# Schematic1P1.net
KiCad netlist of a schematic drawn in Altium Designer
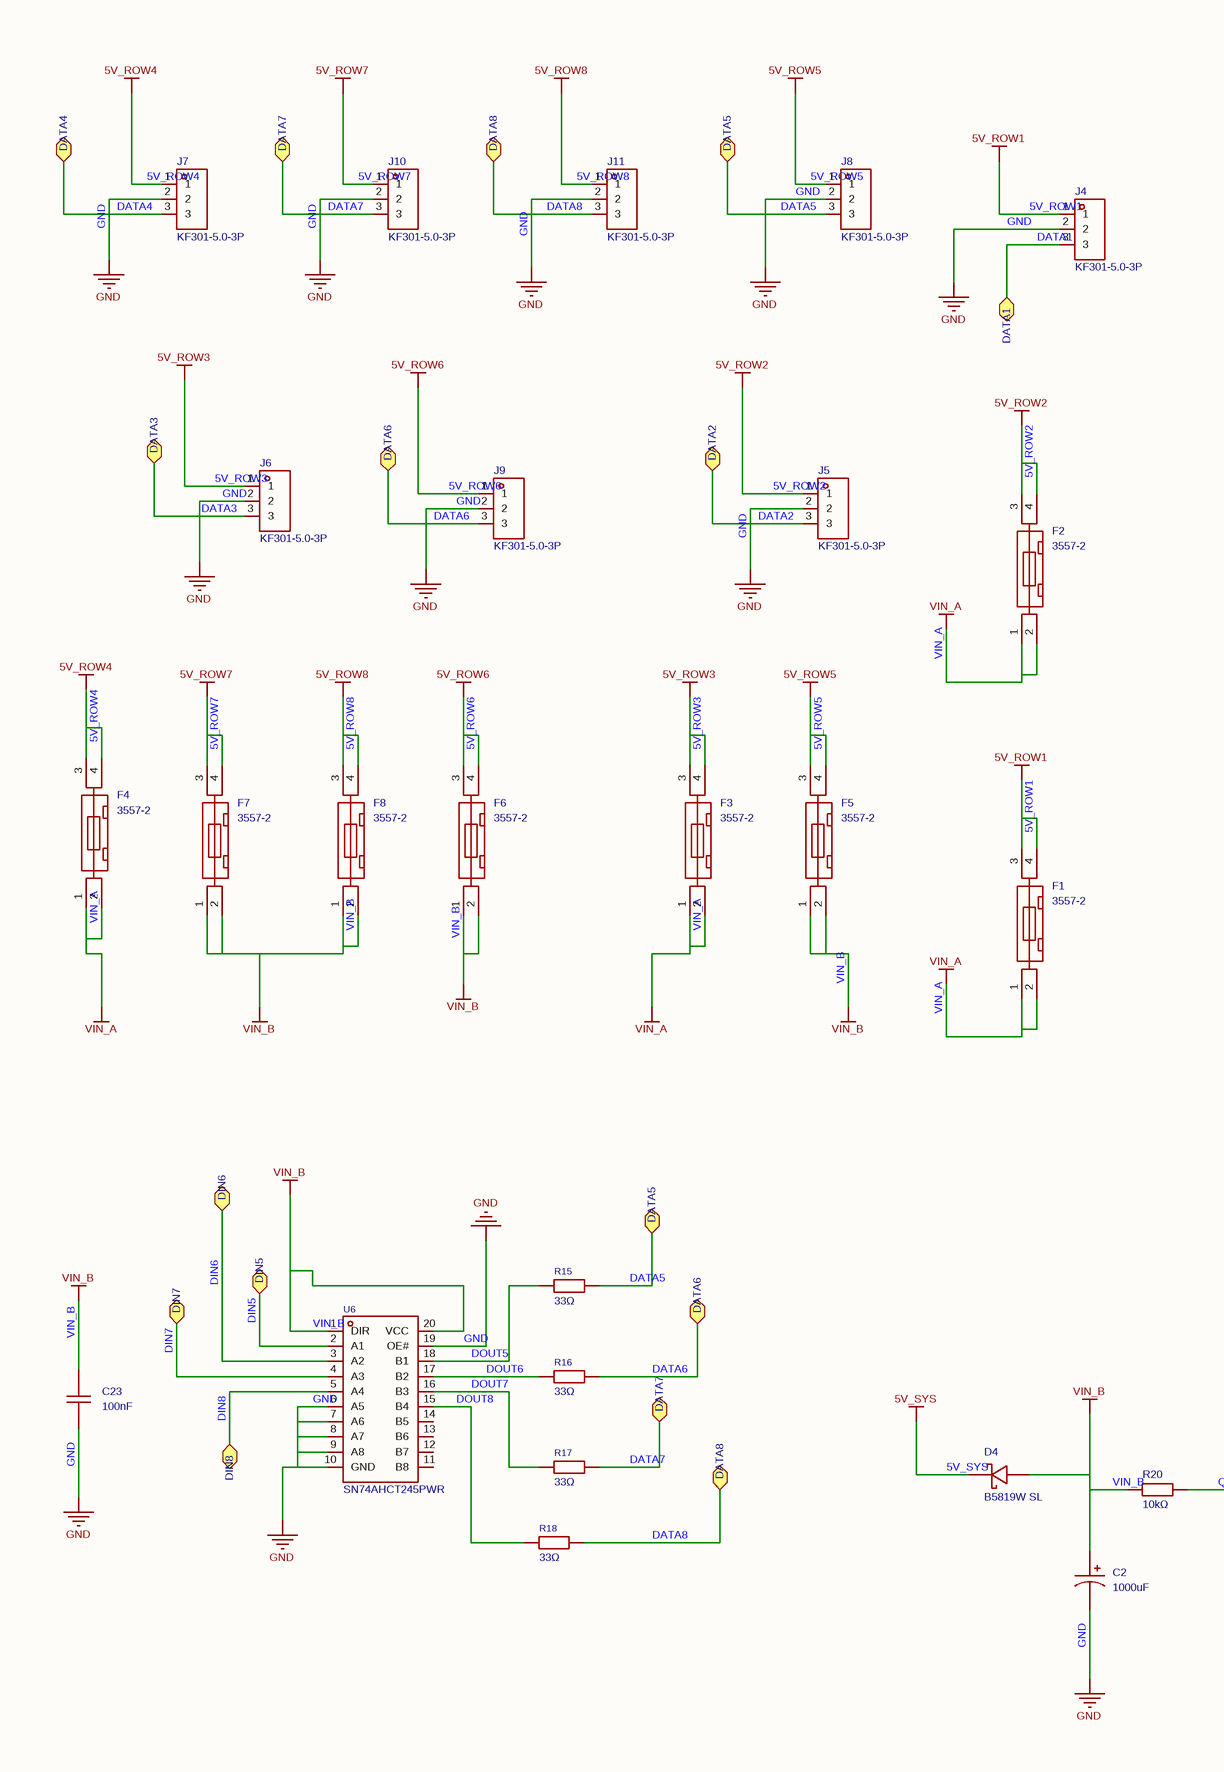
[diagram p0: Schematic1P1.schdoc, left]
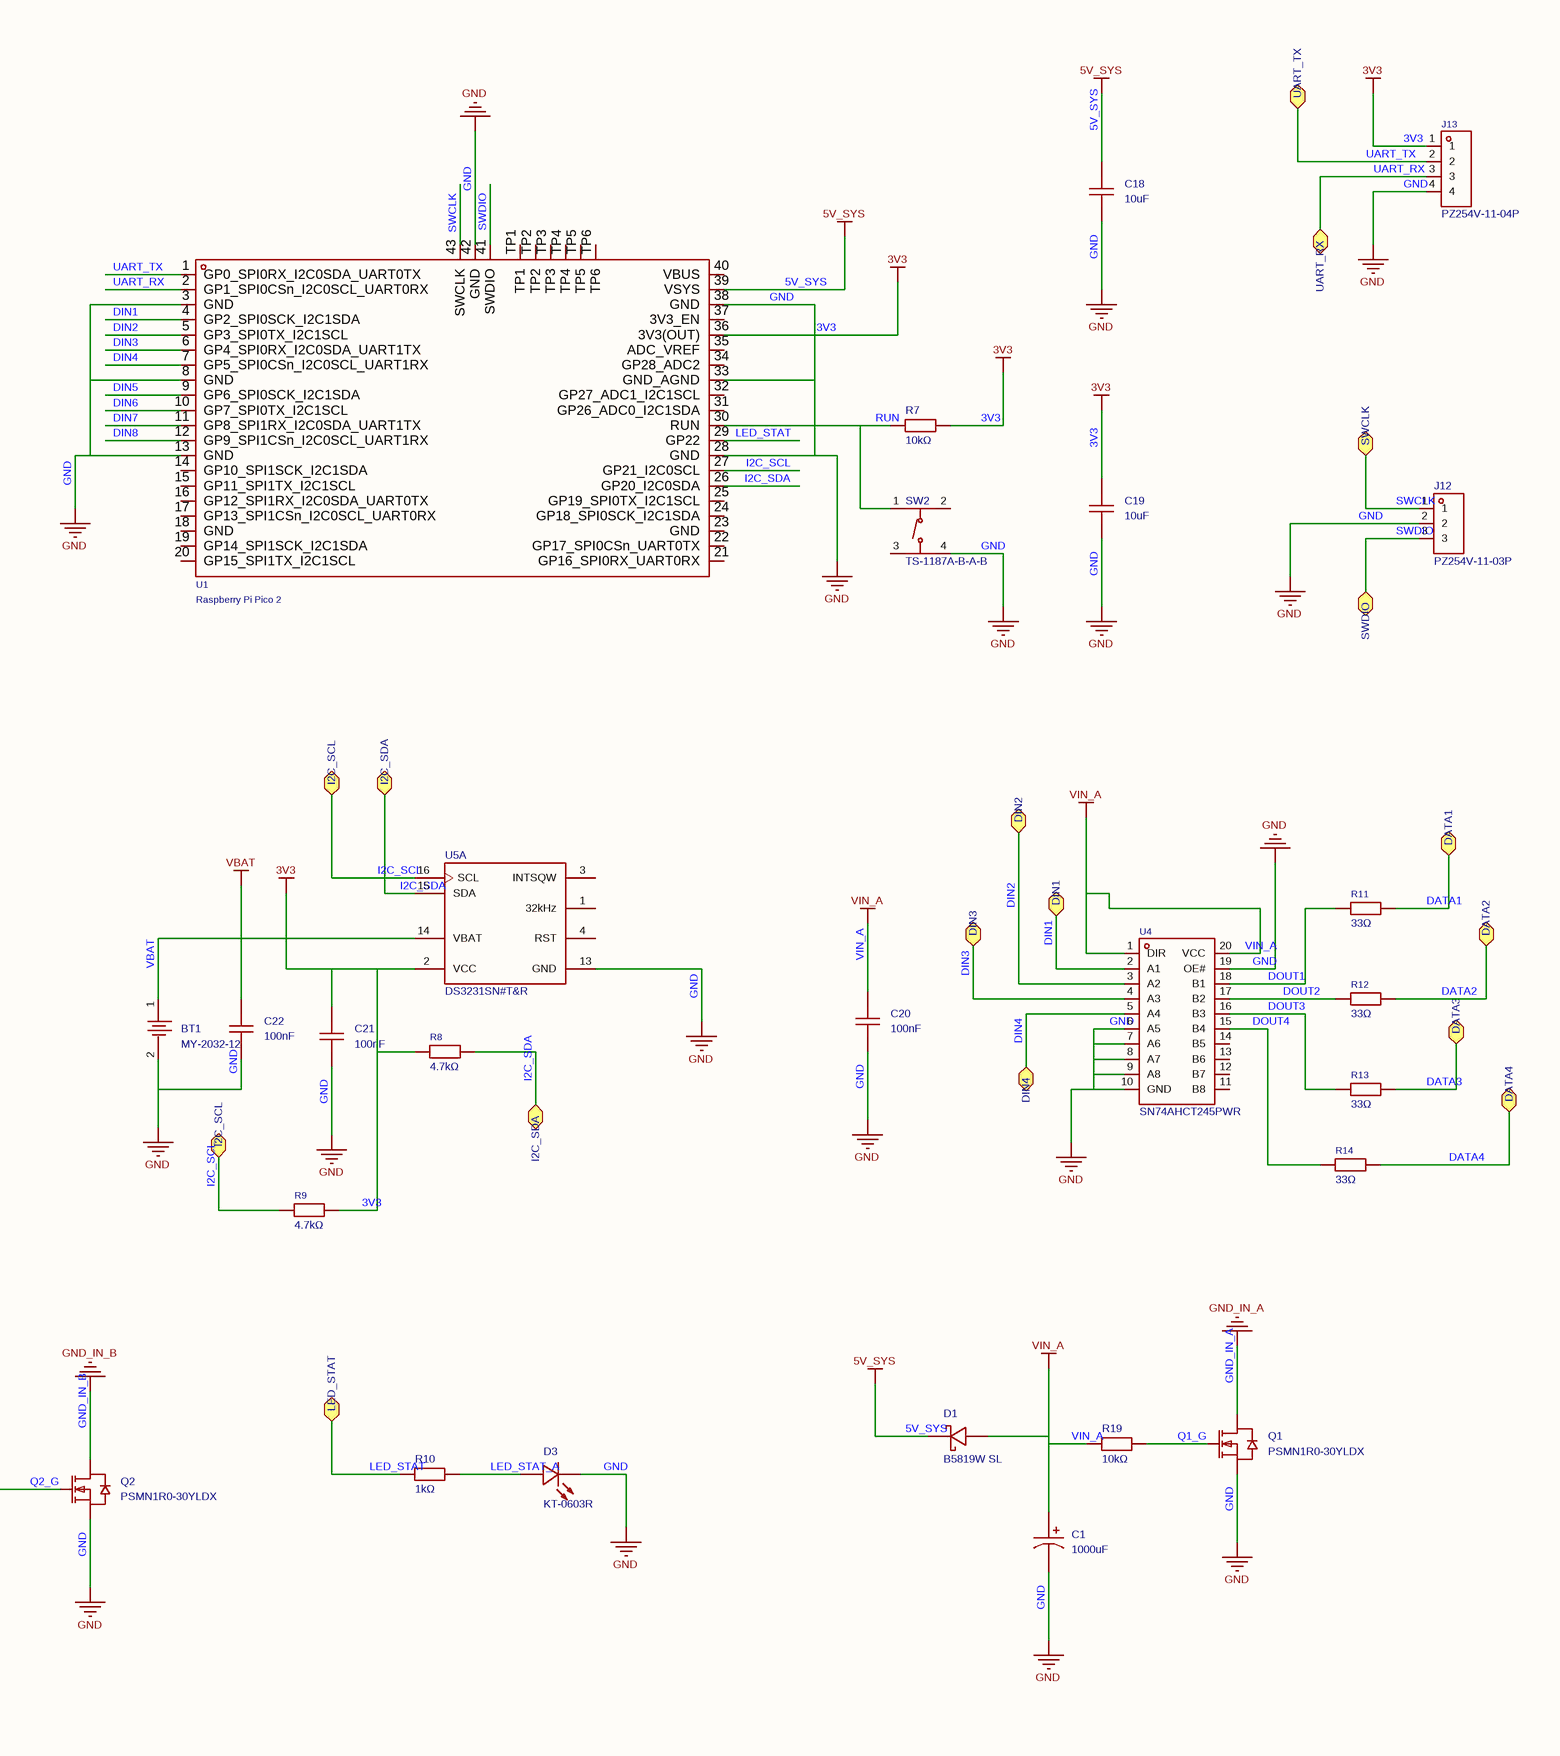
[diagram p1: Schematic1P1.schdoc, right]

(export (version "E")
  (design (tool "Eeschema 10.0.6"))
  (components
    (comp (ref "BT1")
      (value "MY-2032-12")
      (footprint "BAT-SMD_MY-2032-12")
      (fields (field (name "MANUFACTURER") "MYOUNG(美阳)"))
      (libsource (lib "altium-import") (part "root_3_MY-2032-12_"))
    )
    (comp (ref "C1")
      (value "1000uF")
      (footprint "CAP-SMD_BD10.0-L10.3-W10.3-FD")
      (fields
        (field (name "MANUFACTURER") "DMBJ(振宝佳)")
        (field (name "MANUFACTURER PART") "RVT1C102M1010 1000UF 16V")
        (field (name "TOLERANCE") "±20%")
      )
      (libsource (lib "altium-import") (part "root_3_RVT1C102M1010 1000UF 16V_"))
    )
    (comp (ref "C2")
      (value "1000uF")
      (footprint "CAP-SMD_BD10.0-L10.3-W10.3-FD")
      (fields
        (field (name "MANUFACTURER") "DMBJ(振宝佳)")
        (field (name "MANUFACTURER PART") "RVT1C102M1010 1000UF 16V")
        (field (name "TOLERANCE") "±20%")
      )
      (libsource (lib "altium-import") (part "root_3_RVT1C102M1010 1000UF 16V_"))
    )
    (comp (ref "C18")
      (value "10uF")
      (footprint "C0805")
      (description "Capacitance:10uF Tolerance:±10% Tolerance:±10% Voltage Rating:25V Temperature Coefficient:X5R")
      (fields
        (field (name "MANUFACTURER") "SAMSUNG(三星)")
        (field (name "MANUFACTURER PART") "CL21A106KAYNNNE")
      )
      (libsource (lib "altium-import") (part "root_3_CL21A106KAYNNNE_C15850_"))
    )
    (comp (ref "C19")
      (value "10uF")
      (footprint "C0805")
      (description "Capacitance:10uF Tolerance:±10% Tolerance:±10% Voltage Rating:25V Temperature Coefficient:X5R")
      (fields
        (field (name "MANUFACTURER") "SAMSUNG(三星)")
        (field (name "MANUFACTURER PART") "CL21A106KAYNNNE")
      )
      (libsource (lib "altium-import") (part "root_3_CL21A106KAYNNNE_C15850_"))
    )
    (comp (ref "C20")
      (value "100nF")
      (footprint "C0402")
      (description "Capacitance:100nF Tolerance:±10% Tolerance:±10% Voltage Rating:16V Temperature Coefficient:X7R")
      (fields
        (field (name "MANUFACTURER") "SAMSUNG(三星)")
        (field (name "MANUFACTURER PART") "CL05B104KO5NNNC")
      )
      (libsource (lib "altium-import") (part "root_3_CL05B104KO5NNNC_"))
    )
    (comp (ref "C21")
      (value "100nF")
      (footprint "C0402")
      (description "Capacitance:100nF Tolerance:±10% Tolerance:±10% Voltage Rating:16V Temperature Coefficient:X7R")
      (fields
        (field (name "MANUFACTURER") "SAMSUNG(三星)")
        (field (name "MANUFACTURER PART") "CL05B104KO5NNNC")
      )
      (libsource (lib "altium-import") (part "root_3_CL05B104KO5NNNC_"))
    )
    (comp (ref "C22")
      (value "100nF")
      (footprint "C0402")
      (description "Capacitance:100nF Tolerance:±10% Tolerance:±10% Voltage Rating:16V Temperature Coefficient:X7R")
      (fields
        (field (name "MANUFACTURER") "SAMSUNG(三星)")
        (field (name "MANUFACTURER PART") "CL05B104KO5NNNC")
      )
      (libsource (lib "altium-import") (part "root_3_CL05B104KO5NNNC_"))
    )
    (comp (ref "C23")
      (value "100nF")
      (footprint "C0402")
      (description "Capacitance:100nF Tolerance:±10% Tolerance:±10% Voltage Rating:16V Temperature Coefficient:X7R")
      (fields
        (field (name "MANUFACTURER") "SAMSUNG(三星)")
        (field (name "MANUFACTURER PART") "CL05B104KO5NNNC")
      )
      (libsource (lib "altium-import") (part "root_3_CL05B104KO5NNNC_"))
    )
    (comp (ref "D1")
      (value "B5819W SL")
      (footprint "SOD-123_L2.7-W1.6-LS3.7-RD-1")
      (fields (field (name "MANUFACTURER") "CJ(江苏长电/长晶)"))
      (libsource (lib "altium-import") (part "root_0_B5819W SL_"))
    )
    (comp (ref "D3")
      (value "KT-0603R")
      (footprint "LED-SMD_L1.6-W0.8-R-RD")
      (fields (field (name "MANUFACTURER") "KENTO"))
      (libsource (lib "altium-import") (part "root_2_KT-0603R_"))
    )
    (comp (ref "D4")
      (value "B5819W SL")
      (footprint "SOD-123_L2.7-W1.6-LS3.7-RD-1")
      (fields (field (name "MANUFACTURER") "CJ(江苏长电/长晶)"))
      (libsource (lib "altium-import") (part "root_0_B5819W SL_"))
    )
    (comp (ref "F1")
      (value "3557-2")
      (footprint "FUSE-TH_4P-L19.8-W6.7_3557-2")
      (fields (field (name "MANUFACTURER") "Keystone"))
      (libsource (lib "altium-import") (part "root_1_3557-2_"))
    )
    (comp (ref "F2")
      (value "3557-2")
      (footprint "FUSE-TH_4P-L19.8-W6.7_3557-2")
      (fields (field (name "MANUFACTURER") "Keystone"))
      (libsource (lib "altium-import") (part "root_1_3557-2_"))
    )
    (comp (ref "F3")
      (value "3557-2")
      (footprint "FUSE-TH_4P-L19.8-W6.7_3557-2")
      (fields (field (name "MANUFACTURER") "Keystone"))
      (libsource (lib "altium-import") (part "root_1_3557-2_"))
    )
    (comp (ref "F4")
      (value "3557-2")
      (footprint "FUSE-TH_4P-L19.8-W6.7_3557-2")
      (fields (field (name "MANUFACTURER") "Keystone"))
      (libsource (lib "altium-import") (part "root_1_3557-2_"))
    )
    (comp (ref "F5")
      (value "3557-2")
      (footprint "FUSE-TH_4P-L19.8-W6.7_3557-2")
      (fields (field (name "MANUFACTURER") "Keystone"))
      (libsource (lib "altium-import") (part "root_1_3557-2_"))
    )
    (comp (ref "F6")
      (value "3557-2")
      (footprint "FUSE-TH_4P-L19.8-W6.7_3557-2")
      (fields (field (name "MANUFACTURER") "Keystone"))
      (libsource (lib "altium-import") (part "root_1_3557-2_"))
    )
    (comp (ref "F7")
      (value "3557-2")
      (footprint "FUSE-TH_4P-L19.8-W6.7_3557-2")
      (fields (field (name "MANUFACTURER") "Keystone"))
      (libsource (lib "altium-import") (part "root_1_3557-2_"))
    )
    (comp (ref "F8")
      (value "3557-2")
      (footprint "FUSE-TH_4P-L19.8-W6.7_3557-2")
      (fields (field (name "MANUFACTURER") "Keystone"))
      (libsource (lib "altium-import") (part "root_1_3557-2_"))
    )
    (comp (ref "J4")
      (value "KF301-5.0-3P")
      (footprint "CONN-TH_3P-P5.00_KF301-5.0-3P")
      (fields (field (name "MANUFACTURER") "KEFA(科发)"))
      (libsource (lib "altium-import") (part "root_0_KF301-5.0-3P_"))
    )
    (comp (ref "J5")
      (value "KF301-5.0-3P")
      (footprint "CONN-TH_3P-P5.00_KF301-5.0-3P")
      (fields (field (name "MANUFACTURER") "KEFA(科发)"))
      (libsource (lib "altium-import") (part "root_0_KF301-5.0-3P_"))
    )
    (comp (ref "J6")
      (value "KF301-5.0-3P")
      (footprint "CONN-TH_3P-P5.00_KF301-5.0-3P")
      (fields (field (name "MANUFACTURER") "KEFA(科发)"))
      (libsource (lib "altium-import") (part "root_0_KF301-5.0-3P_"))
    )
    (comp (ref "J7")
      (value "KF301-5.0-3P")
      (footprint "CONN-TH_3P-P5.00_KF301-5.0-3P")
      (fields (field (name "MANUFACTURER") "KEFA(科发)"))
      (libsource (lib "altium-import") (part "root_0_KF301-5.0-3P_"))
    )
    (comp (ref "J8")
      (value "KF301-5.0-3P")
      (footprint "CONN-TH_3P-P5.00_KF301-5.0-3P")
      (fields (field (name "MANUFACTURER") "KEFA(科发)"))
      (libsource (lib "altium-import") (part "root_0_KF301-5.0-3P_"))
    )
    (comp (ref "J9")
      (value "KF301-5.0-3P")
      (footprint "CONN-TH_3P-P5.00_KF301-5.0-3P")
      (fields (field (name "MANUFACTURER") "KEFA(科发)"))
      (libsource (lib "altium-import") (part "root_0_KF301-5.0-3P_"))
    )
    (comp (ref "J10")
      (value "KF301-5.0-3P")
      (footprint "CONN-TH_3P-P5.00_KF301-5.0-3P")
      (fields (field (name "MANUFACTURER") "KEFA(科发)"))
      (libsource (lib "altium-import") (part "root_0_KF301-5.0-3P_"))
    )
    (comp (ref "J11")
      (value "KF301-5.0-3P")
      (footprint "CONN-TH_3P-P5.00_KF301-5.0-3P")
      (fields (field (name "MANUFACTURER") "KEFA(科发)"))
      (libsource (lib "altium-import") (part "root_0_KF301-5.0-3P_"))
    )
    (comp (ref "J12")
      (value "PZ254V-11-03P")
      (footprint "HDR-TH_3P-P2.54-V-M")
      (fields (field (name "MANUFACTURER") "XFCN(兴飞)"))
      (libsource (lib "altium-import") (part "root_0_PZ254V-11-03P_C492402_"))
    )
    (comp (ref "J13")
      (value "PZ254V-11-04P")
      (footprint "HDR-TH_4P-P2.54-V-M")
      (fields (field (name "MANUFACTURER") "XFCN(兴飞)"))
      (libsource (lib "altium-import") (part "root_0_PZ254V-11-04P_"))
    )
    (comp (ref "Q1")
      (value "PSMN1R0-30YLDX")
      (footprint "LFPAK56-4_L4.9-W4.2-P1.27-LS6.2-BL")
      (fields (field (name "MANUFACTURER") "Nexperia(安世)"))
      (libsource (lib "altium-import") (part "root_0_PSMN1R0-30YLDX_"))
    )
    (comp (ref "Q2")
      (value "PSMN1R0-30YLDX")
      (footprint "LFPAK56-4_L4.9-W4.2-P1.27-LS6.2-BL")
      (fields (field (name "MANUFACTURER") "Nexperia(安世)"))
      (libsource (lib "altium-import") (part "root_0_PSMN1R0-30YLDX_"))
    )
    (comp (ref "R7")
      (value "10kΩ")
      (footprint "R0402")
      (fields
        (field (name "MANUFACTURER") "UNI-ROYAL(厚声)")
        (field (name "MANUFACTURER PART") "0402WGF1002TCE")
        (field (name "TOLERANCE") "±1%")
      )
      (libsource (lib "altium-import") (part "root_0_0402WGF1002TCE_"))
    )
    (comp (ref "R8")
      (value "4.7kΩ")
      (footprint "R0402")
      (fields
        (field (name "TOLERANCE") "±1%")
        (field (name "MANUFACTURER") "UNI-ROYAL(厚声)")
        (field (name "MANUFACTURER PART") "0402WGF4701TCE")
      )
      (libsource (lib "altium-import") (part "root_2_0402WGF4701TCE_"))
    )
    (comp (ref "R9")
      (value "4.7kΩ")
      (footprint "R0402")
      (fields
        (field (name "MANUFACTURER") "UNI-ROYAL(厚声)")
        (field (name "MANUFACTURER PART") "0402WGF4701TCE")
        (field (name "TOLERANCE") "±1%")
      )
      (libsource (lib "altium-import") (part "root_0_0402WGF4701TCE_"))
    )
    (comp (ref "R10")
      (value "1kΩ")
      (footprint "R0402")
      (fields
        (field (name "MANUFACTURER") "UNI-ROYAL(厚声)")
        (field (name "MANUFACTURER PART") "0402WGF1001TCE")
        (field (name "TOLERANCE") "±1%")
      )
      (libsource (lib "altium-import") (part "root_0_0402WGF1001TCE_"))
    )
    (comp (ref "R11")
      (value "33Ω")
      (footprint "R0402")
      (fields
        (field (name "TOLERANCE") "±1%")
        (field (name "MANUFACTURER") "UNI-ROYAL(厚声)")
        (field (name "MANUFACTURER PART") "0402WGF330JTCE")
      )
      (libsource (lib "altium-import") (part "root_0_0402WGF330JTCE_"))
    )
    (comp (ref "R12")
      (value "33Ω")
      (footprint "R0402")
      (fields
        (field (name "MANUFACTURER") "UNI-ROYAL(厚声)")
        (field (name "MANUFACTURER PART") "0402WGF330JTCE")
        (field (name "TOLERANCE") "±1%")
      )
      (libsource (lib "altium-import") (part "root_0_0402WGF330JTCE_"))
    )
    (comp (ref "R13")
      (value "33Ω")
      (footprint "R0402")
      (fields
        (field (name "MANUFACTURER") "UNI-ROYAL(厚声)")
        (field (name "MANUFACTURER PART") "0402WGF330JTCE")
        (field (name "TOLERANCE") "±1%")
      )
      (libsource (lib "altium-import") (part "root_0_0402WGF330JTCE_"))
    )
    (comp (ref "R14")
      (value "33Ω")
      (footprint "R0402")
      (fields
        (field (name "MANUFACTURER") "UNI-ROYAL(厚声)")
        (field (name "MANUFACTURER PART") "0402WGF330JTCE")
        (field (name "TOLERANCE") "±1%")
      )
      (libsource (lib "altium-import") (part "root_0_0402WGF330JTCE_"))
    )
    (comp (ref "R15")
      (value "33Ω")
      (footprint "R0402")
      (fields
        (field (name "MANUFACTURER") "UNI-ROYAL(厚声)")
        (field (name "MANUFACTURER PART") "0402WGF330JTCE")
        (field (name "TOLERANCE") "±1%")
      )
      (libsource (lib "altium-import") (part "root_0_0402WGF330JTCE_"))
    )
    (comp (ref "R16")
      (value "33Ω")
      (footprint "R0402")
      (fields
        (field (name "MANUFACTURER") "UNI-ROYAL(厚声)")
        (field (name "MANUFACTURER PART") "0402WGF330JTCE")
        (field (name "TOLERANCE") "±1%")
      )
      (libsource (lib "altium-import") (part "root_0_0402WGF330JTCE_"))
    )
    (comp (ref "R17")
      (value "33Ω")
      (footprint "R0402")
      (fields
        (field (name "MANUFACTURER") "UNI-ROYAL(厚声)")
        (field (name "MANUFACTURER PART") "0402WGF330JTCE")
        (field (name "TOLERANCE") "±1%")
      )
      (libsource (lib "altium-import") (part "root_0_0402WGF330JTCE_"))
    )
    (comp (ref "R18")
      (value "33Ω")
      (footprint "R0402")
      (fields
        (field (name "MANUFACTURER") "UNI-ROYAL(厚声)")
        (field (name "MANUFACTURER PART") "0402WGF330JTCE")
        (field (name "TOLERANCE") "±1%")
      )
      (libsource (lib "altium-import") (part "root_0_0402WGF330JTCE_"))
    )
    (comp (ref "R19")
      (value "10kΩ")
      (footprint "R0402")
      (fields
        (field (name "MANUFACTURER") "UNI-ROYAL(厚声)")
        (field (name "MANUFACTURER PART") "0402WGF1002TCE")
        (field (name "TOLERANCE") "±1%")
      )
      (libsource (lib "altium-import") (part "root_0_0402WGF1002TCE_"))
    )
    (comp (ref "R20")
      (value "10kΩ")
      (footprint "R0402")
      (fields
        (field (name "MANUFACTURER") "UNI-ROYAL(厚声)")
        (field (name "MANUFACTURER PART") "0402WGF1002TCE")
        (field (name "TOLERANCE") "±1%")
      )
      (libsource (lib "altium-import") (part "root_0_0402WGF1002TCE_"))
    )
    (comp (ref "SW2")
      (value "TS-1187A-B-A-B")
      (footprint "SW-SMD_4P-L5.1-W5.1-P3.70-LS6.5-TL_H1.5")
      (fields (field (name "MANUFACTURER") "XKB Connection(中国星坤)"))
      (libsource (lib "altium-import") (part "root_0_TS-1187A-B-A-B_"))
    )
    (comp (ref "U1")
      (value "Raspberry Pi Pico 2")
      (footprint "COMM-SMD_L51.0-W21.0-P2.54_SC0916")
      (fields (field (name "MANUFACTURER") "Raspberry Pi(树莓派)"))
      (libsource (lib "altium-import") (part "root_0_Raspberry Pi Pico 2_"))
    )
    (comp (ref "U4")
      (value "SN74AHCT245PWR")
      (footprint "TSSOP-20_L6.5-W4.4-P0.65-LS6.4-BL")
      (fields (field (name "MANUFACTURER") "TI(德州仪器)"))
      (libsource (lib "altium-import") (part "root_0_SN74AHCT245PWR_"))
    )
    (comp (ref "U5")
      (value "DS3231SN#T&R")
      (footprint "SOIC-16_L10.3-W7.5-P1.27-LS10.3-BL")
      (fields (field (name "MANUFACTURER") "ADI(亚德诺)/MAXIM(美信)"))
      (libsource (lib "altium-import") (part "root_0_DS3231SN#T&R_"))
    )
    (comp (ref "U6")
      (value "SN74AHCT245PWR")
      (footprint "TSSOP-20_L6.5-W4.4-P0.65-LS6.4-BL")
      (fields (field (name "MANUFACTURER") "TI(德州仪器)"))
      (libsource (lib "altium-import") (part "root_0_SN74AHCT245PWR_"))
    )
  )
  (nets
    (net (code "1") (name "/DATA1") (class "Default")
      (node (ref "J4") (pin "3") (pinfunction "3_3") (pintype "passive"))
      (node (ref "R11") (pin "2") (pinfunction "2_2") (pintype "passive"))
    )
    (net (code "2") (name "/DATA2") (class "Default")
      (node (ref "J5") (pin "3") (pinfunction "3_3") (pintype "passive"))
      (node (ref "R12") (pin "2") (pinfunction "2_2") (pintype "passive"))
    )
    (net (code "3") (name "/DATA3") (class "Default")
      (node (ref "J6") (pin "3") (pinfunction "3_3") (pintype "passive"))
      (node (ref "R13") (pin "2") (pinfunction "2_2") (pintype "passive"))
    )
    (net (code "4") (name "/DATA4") (class "Default")
      (node (ref "J7") (pin "3") (pinfunction "3_3") (pintype "passive"))
      (node (ref "R14") (pin "2") (pinfunction "2_2") (pintype "passive"))
    )
    (net (code "5") (name "/DATA5") (class "Default")
      (node (ref "J8") (pin "3") (pinfunction "3_3") (pintype "passive"))
      (node (ref "R15") (pin "2") (pinfunction "2_2") (pintype "passive"))
    )
    (net (code "6") (name "/DATA6") (class "Default")
      (node (ref "J9") (pin "3") (pinfunction "3_3") (pintype "passive"))
      (node (ref "R16") (pin "2") (pinfunction "2_2") (pintype "passive"))
    )
    (net (code "7") (name "/DATA7") (class "Default")
      (node (ref "J10") (pin "3") (pinfunction "3_3") (pintype "passive"))
      (node (ref "R17") (pin "2") (pinfunction "2_2") (pintype "passive"))
    )
    (net (code "8") (name "/DATA8") (class "Default")
      (node (ref "J11") (pin "3") (pinfunction "3_3") (pintype "passive"))
      (node (ref "R18") (pin "2") (pinfunction "2_2") (pintype "passive"))
    )
    (net (code "9") (name "/DIN1") (class "Default")
      (node (ref "U1") (pin "4") (pinfunction "GP2_SPI0SCK_I2C1SDA_4") (pintype "passive"))
      (node (ref "U4") (pin "2") (pinfunction "A1_2") (pintype "passive"))
    )
    (net (code "10") (name "/DIN2") (class "Default")
      (node (ref "U1") (pin "5") (pinfunction "GP3_SPI0TX_I2C1SCL_5") (pintype "passive"))
      (node (ref "U4") (pin "3") (pinfunction "A2_3") (pintype "passive"))
    )
    (net (code "11") (name "/DIN3") (class "Default")
      (node (ref "U1") (pin "6") (pinfunction "GP4_SPI0RX_I2C0SDA_UART1TX_6") (pintype "passive"))
      (node (ref "U4") (pin "4") (pinfunction "A3_4") (pintype "passive"))
    )
    (net (code "12") (name "/DIN4") (class "Default")
      (node (ref "U1") (pin "7") (pinfunction "GP5_SPI0CSn_I2C0SCL_UART1RX_7") (pintype "passive"))
      (node (ref "U4") (pin "5") (pinfunction "A4_5") (pintype "passive"))
    )
    (net (code "13") (name "/DIN5") (class "Default")
      (node (ref "U1") (pin "9") (pinfunction "GP6_SPI0SCK_I2C1SDA_9") (pintype "passive"))
      (node (ref "U6") (pin "2") (pinfunction "A1_2") (pintype "passive"))
    )
    (net (code "14") (name "/DIN6") (class "Default")
      (node (ref "U1") (pin "10") (pinfunction "GP7_SPI0TX_I2C1SCL_10") (pintype "passive"))
      (node (ref "U6") (pin "3") (pinfunction "A2_3") (pintype "passive"))
    )
    (net (code "15") (name "/DIN7") (class "Default")
      (node (ref "U1") (pin "11") (pinfunction "GP8_SPI1RX_I2C0SDA_UART1TX_11") (pintype "passive"))
      (node (ref "U6") (pin "4") (pinfunction "A3_4") (pintype "passive"))
    )
    (net (code "16") (name "/DIN8") (class "Default")
      (node (ref "U1") (pin "12") (pinfunction "GP9_SPI1CSn_I2C0SCL_UART1RX_12") (pintype "passive"))
      (node (ref "U6") (pin "5") (pinfunction "A4_5") (pintype "passive"))
    )
    (net (code "17") (name "/DOUT1") (class "Default")
      (node (ref "R11") (pin "1") (pinfunction "1_1") (pintype "passive"))
      (node (ref "U4") (pin "18") (pinfunction "B1_18") (pintype "passive"))
    )
    (net (code "18") (name "/DOUT2") (class "Default")
      (node (ref "R12") (pin "1") (pinfunction "1_1") (pintype "passive"))
      (node (ref "U4") (pin "17") (pinfunction "B2_17") (pintype "passive"))
    )
    (net (code "19") (name "/DOUT3") (class "Default")
      (node (ref "R13") (pin "1") (pinfunction "1_1") (pintype "passive"))
      (node (ref "U4") (pin "16") (pinfunction "B3_16") (pintype "passive"))
    )
    (net (code "20") (name "/DOUT4") (class "Default")
      (node (ref "R14") (pin "1") (pinfunction "1_1") (pintype "passive"))
      (node (ref "U4") (pin "15") (pinfunction "B4_15") (pintype "passive"))
    )
    (net (code "21") (name "/DOUT5") (class "Default")
      (node (ref "R15") (pin "1") (pinfunction "1_1") (pintype "passive"))
      (node (ref "U6") (pin "18") (pinfunction "B1_18") (pintype "passive"))
    )
    (net (code "22") (name "/DOUT6") (class "Default")
      (node (ref "R16") (pin "1") (pinfunction "1_1") (pintype "passive"))
      (node (ref "U6") (pin "17") (pinfunction "B2_17") (pintype "passive"))
    )
    (net (code "23") (name "/DOUT7") (class "Default")
      (node (ref "R17") (pin "1") (pinfunction "1_1") (pintype "passive"))
      (node (ref "U6") (pin "16") (pinfunction "B3_16") (pintype "passive"))
    )
    (net (code "24") (name "/DOUT8") (class "Default")
      (node (ref "R18") (pin "1") (pinfunction "1_1") (pintype "passive"))
      (node (ref "U6") (pin "15") (pinfunction "B4_15") (pintype "passive"))
    )
    (net (code "25") (name "/I2C_SCL") (class "Default")
      (node (ref "R9") (pin "1") (pinfunction "1_1") (pintype "passive"))
      (node (ref "U1") (pin "27") (pinfunction "GP21_I2C0SCL_27") (pintype "passive"))
      (node (ref "U5") (pin "16") (pinfunction "SCL_16") (pintype "passive"))
    )
    (net (code "26") (name "/I2C_SDA") (class "Default")
      (node (ref "R8") (pin "1") (pinfunction "1_1") (pintype "passive"))
      (node (ref "U1") (pin "26") (pinfunction "GP20_I2C0SDA_26") (pintype "passive"))
      (node (ref "U5") (pin "15") (pinfunction "SDA_15") (pintype "passive"))
    )
    (net (code "27") (name "/LED_STAT") (class "Default")
      (node (ref "R10") (pin "1") (pinfunction "1_1") (pintype "passive"))
      (node (ref "U1") (pin "29") (pinfunction "GP22_29") (pintype "passive"))
    )
    (net (code "28") (name "/LED_STAT_A") (class "Default")
      (node (ref "D3") (pin "1") (pinfunction "A_1") (pintype "passive"))
      (node (ref "R10") (pin "2") (pinfunction "2_2") (pintype "passive"))
    )
    (net (code "29") (name "/Q1_G") (class "Default")
      (node (ref "Q1") (pin "4") (pinfunction "G_4") (pintype "passive"))
      (node (ref "R19") (pin "2") (pinfunction "2_2") (pintype "passive"))
    )
    (net (code "30") (name "/Q2_G") (class "Default")
      (node (ref "Q2") (pin "4") (pinfunction "G_4") (pintype "passive"))
      (node (ref "R20") (pin "2") (pinfunction "2_2") (pintype "passive"))
    )
    (net (code "31") (name "/RUN") (class "Default")
      (node (ref "R7") (pin "1") (pinfunction "1_1") (pintype "passive"))
      (node (ref "SW2") (pin "1") (pinfunction "A_1") (pintype "passive"))
      (node (ref "U1") (pin "30") (pinfunction "RUN_30") (pintype "passive"))
    )
    (net (code "32") (name "/SWCLK") (class "Default")
      (node (ref "J12") (pin "1") (pinfunction "1_1") (pintype "passive"))
      (node (ref "U1") (pin "43") (pinfunction "SWCLK_43") (pintype "passive"))
    )
    (net (code "33") (name "/SWDIO") (class "Default")
      (node (ref "J12") (pin "3") (pinfunction "3_3") (pintype "passive"))
      (node (ref "U1") (pin "41") (pinfunction "SWDIO_41") (pintype "passive"))
    )
    (net (code "34") (name "/UART_RX") (class "Default")
      (node (ref "J13") (pin "3") (pinfunction "3_3") (pintype "passive"))
      (node (ref "U1") (pin "2") (pinfunction "GP1_SPI0CSn_I2C0SCL_UART0RX_2") (pintype "passive"))
    )
    (net (code "35") (name "/UART_TX") (class "Default")
      (node (ref "J13") (pin "2") (pinfunction "2_2") (pintype "passive"))
      (node (ref "U1") (pin "1") (pinfunction "GP0_SPI0RX_I2C0SDA_UART0TX_1") (pintype "passive"))
    )
    (net (code "36") (name "3V3") (class "Default")
      (node (ref "C19") (pin "1") (pinfunction "1_1") (pintype "passive"))
      (node (ref "C21") (pin "1") (pinfunction "1_1") (pintype "passive"))
      (node (ref "J13") (pin "1") (pinfunction "1_1") (pintype "passive"))
      (node (ref "R7") (pin "2") (pinfunction "2_2") (pintype "passive"))
      (node (ref "R8") (pin "2") (pinfunction "2_2") (pintype "passive"))
      (node (ref "R9") (pin "2") (pinfunction "2_2") (pintype "passive"))
      (node (ref "U1") (pin "36") (pinfunction "3V3(OUT)_36") (pintype "passive"))
      (node (ref "U5") (pin "2") (pinfunction "VCC_2") (pintype "passive"))
    )
    (net (code "37") (name "5V_ROW1") (class "Default")
      (node (ref "F1") (pin "3") (pinfunction "3_3") (pintype "passive"))
      (node (ref "F1") (pin "4") (pinfunction "4_4") (pintype "passive"))
      (node (ref "J4") (pin "1") (pinfunction "1_1") (pintype "passive"))
    )
    (net (code "38") (name "5V_ROW2") (class "Default")
      (node (ref "F2") (pin "3") (pinfunction "3_3") (pintype "passive"))
      (node (ref "F2") (pin "4") (pinfunction "4_4") (pintype "passive"))
      (node (ref "J5") (pin "1") (pinfunction "1_1") (pintype "passive"))
    )
    (net (code "39") (name "5V_ROW3") (class "Default")
      (node (ref "F3") (pin "3") (pinfunction "3_3") (pintype "passive"))
      (node (ref "F3") (pin "4") (pinfunction "4_4") (pintype "passive"))
      (node (ref "J6") (pin "1") (pinfunction "1_1") (pintype "passive"))
    )
    (net (code "40") (name "5V_ROW4") (class "Default")
      (node (ref "F4") (pin "3") (pinfunction "3_3") (pintype "passive"))
      (node (ref "F4") (pin "4") (pinfunction "4_4") (pintype "passive"))
      (node (ref "J7") (pin "1") (pinfunction "1_1") (pintype "passive"))
    )
    (net (code "41") (name "5V_ROW5") (class "Default")
      (node (ref "F5") (pin "3") (pinfunction "3_3") (pintype "passive"))
      (node (ref "F5") (pin "4") (pinfunction "4_4") (pintype "passive"))
      (node (ref "J8") (pin "1") (pinfunction "1_1") (pintype "passive"))
    )
    (net (code "42") (name "5V_ROW6") (class "Default")
      (node (ref "F6") (pin "3") (pinfunction "3_3") (pintype "passive"))
      (node (ref "F6") (pin "4") (pinfunction "4_4") (pintype "passive"))
      (node (ref "J9") (pin "1") (pinfunction "1_1") (pintype "passive"))
    )
    (net (code "43") (name "5V_ROW7") (class "Default")
      (node (ref "F7") (pin "3") (pinfunction "3_3") (pintype "passive"))
      (node (ref "F7") (pin "4") (pinfunction "4_4") (pintype "passive"))
      (node (ref "J10") (pin "1") (pinfunction "1_1") (pintype "passive"))
    )
    (net (code "44") (name "5V_ROW8") (class "Default")
      (node (ref "F8") (pin "3") (pinfunction "3_3") (pintype "passive"))
      (node (ref "F8") (pin "4") (pinfunction "4_4") (pintype "passive"))
      (node (ref "J11") (pin "1") (pinfunction "1_1") (pintype "passive"))
    )
    (net (code "45") (name "5V_SYS") (class "Default")
      (node (ref "C18") (pin "1") (pinfunction "1_1") (pintype "passive"))
      (node (ref "D1") (pin "1") (pinfunction "-_1") (pintype "passive"))
      (node (ref "D4") (pin "1") (pinfunction "-_1") (pintype "passive"))
      (node (ref "U1") (pin "39") (pinfunction "VSYS_39") (pintype "passive"))
    )
    (net (code "46") (name "GND") (class "Default")
      (node (ref "BT1") (pin "2") (pinfunction "2_2") (pintype "passive"))
      (node (ref "C1") (pin "2") (pinfunction "2_2") (pintype "passive"))
      (node (ref "C18") (pin "2") (pinfunction "2_2") (pintype "passive"))
      (node (ref "C19") (pin "2") (pinfunction "2_2") (pintype "passive"))
      (node (ref "C2") (pin "2") (pinfunction "2_2") (pintype "passive"))
      (node (ref "C20") (pin "2") (pinfunction "2_2") (pintype "passive"))
      (node (ref "C21") (pin "2") (pinfunction "2_2") (pintype "passive"))
      (node (ref "C22") (pin "2") (pinfunction "2_2") (pintype "passive"))
      (node (ref "C23") (pin "2") (pinfunction "2_2") (pintype "passive"))
      (node (ref "D3") (pin "2") (pinfunction "K_2") (pintype "passive"))
      (node (ref "J10") (pin "2") (pinfunction "2_2") (pintype "passive"))
      (node (ref "J11") (pin "2") (pinfunction "2_2") (pintype "passive"))
      (node (ref "J12") (pin "2") (pinfunction "2_2") (pintype "passive"))
      (node (ref "J13") (pin "4") (pinfunction "4_4") (pintype "passive"))
      (node (ref "J4") (pin "2") (pinfunction "2_2") (pintype "passive"))
      (node (ref "J5") (pin "2") (pinfunction "2_2") (pintype "passive"))
      (node (ref "J6") (pin "2") (pinfunction "2_2") (pintype "passive"))
      (node (ref "J7") (pin "2") (pinfunction "2_2") (pintype "passive"))
      (node (ref "J8") (pin "2") (pinfunction "2_2") (pintype "passive"))
      (node (ref "J9") (pin "2") (pinfunction "2_2") (pintype "passive"))
      (node (ref "Q1") (pin "1") (pinfunction "S_1") (pintype "passive"))
      (node (ref "Q1") (pin "2") (pinfunction "S_2") (pintype "passive"))
      (node (ref "Q1") (pin "3") (pinfunction "S_3") (pintype "passive"))
      (node (ref "Q2") (pin "1") (pinfunction "S_1") (pintype "passive"))
      (node (ref "Q2") (pin "2") (pinfunction "S_2") (pintype "passive"))
      (node (ref "Q2") (pin "3") (pinfunction "S_3") (pintype "passive"))
      (node (ref "SW2") (pin "4") (pinfunction "D_4") (pintype "passive"))
      (node (ref "U1") (pin "13") (pinfunction "GND_13") (pintype "passive"))
      (node (ref "U1") (pin "28") (pinfunction "GND_28") (pintype "passive"))
      (node (ref "U1") (pin "3") (pinfunction "GND_3") (pintype "passive"))
      (node (ref "U1") (pin "33") (pinfunction "GND_AGND_33") (pintype "passive"))
      (node (ref "U1") (pin "38") (pinfunction "GND_38") (pintype "passive"))
      (node (ref "U1") (pin "42") (pinfunction "GND_42") (pintype "passive"))
      (node (ref "U1") (pin "8") (pinfunction "GND_8") (pintype "passive"))
      (node (ref "U4") (pin "10") (pinfunction "GND_10") (pintype "passive"))
      (node (ref "U4") (pin "19") (pinfunction "OE#_19") (pintype "passive"))
      (node (ref "U4") (pin "6") (pinfunction "A5_6") (pintype "passive"))
      (node (ref "U4") (pin "7") (pinfunction "A6_7") (pintype "passive"))
      (node (ref "U4") (pin "8") (pinfunction "A7_8") (pintype "passive"))
      (node (ref "U4") (pin "9") (pinfunction "A8_9") (pintype "passive"))
      (node (ref "U5") (pin "13") (pinfunction "GND_13") (pintype "passive"))
      (node (ref "U6") (pin "10") (pinfunction "GND_10") (pintype "passive"))
      (node (ref "U6") (pin "19") (pinfunction "OE#_19") (pintype "passive"))
      (node (ref "U6") (pin "6") (pinfunction "A5_6") (pintype "passive"))
      (node (ref "U6") (pin "7") (pinfunction "A6_7") (pintype "passive"))
      (node (ref "U6") (pin "8") (pinfunction "A7_8") (pintype "passive"))
      (node (ref "U6") (pin "9") (pinfunction "A8_9") (pintype "passive"))
    )
    (net (code "47") (name "GND_IN_A") (class "Default")
      (node (ref "Q1") (pin "5") (pinfunction "D_5") (pintype "passive"))
    )
    (net (code "48") (name "GND_IN_B") (class "Default")
      (node (ref "Q2") (pin "5") (pinfunction "D_5") (pintype "passive"))
    )
    (net (code "49") (name "VBAT") (class "Default")
      (node (ref "BT1") (pin "1") (pinfunction "1_1") (pintype "passive"))
      (node (ref "C22") (pin "1") (pinfunction "1_1") (pintype "passive"))
      (node (ref "U5") (pin "14") (pinfunction "VBAT_14") (pintype "passive"))
    )
    (net (code "50") (name "VIN_A") (class "Default")
      (node (ref "C1") (pin "1") (pinfunction "1_1") (pintype "passive"))
      (node (ref "C20") (pin "1") (pinfunction "1_1") (pintype "passive"))
      (node (ref "D1") (pin "2") (pinfunction "+_2") (pintype "passive"))
      (node (ref "F1") (pin "1") (pinfunction "1_1") (pintype "passive"))
      (node (ref "F1") (pin "2") (pinfunction "2_2") (pintype "passive"))
      (node (ref "F2") (pin "1") (pinfunction "1_1") (pintype "passive"))
      (node (ref "F2") (pin "2") (pinfunction "2_2") (pintype "passive"))
      (node (ref "F3") (pin "1") (pinfunction "1_1") (pintype "passive"))
      (node (ref "F3") (pin "2") (pinfunction "2_2") (pintype "passive"))
      (node (ref "F4") (pin "1") (pinfunction "1_1") (pintype "passive"))
      (node (ref "F4") (pin "2") (pinfunction "2_2") (pintype "passive"))
      (node (ref "R19") (pin "1") (pinfunction "1_1") (pintype "passive"))
      (node (ref "U4") (pin "1") (pinfunction "DIR_1") (pintype "passive"))
      (node (ref "U4") (pin "20") (pinfunction "VCC_20") (pintype "passive"))
    )
    (net (code "51") (name "VIN_B") (class "Default")
      (node (ref "C2") (pin "1") (pinfunction "1_1") (pintype "passive"))
      (node (ref "C23") (pin "1") (pinfunction "1_1") (pintype "passive"))
      (node (ref "D4") (pin "2") (pinfunction "+_2") (pintype "passive"))
      (node (ref "F5") (pin "1") (pinfunction "1_1") (pintype "passive"))
      (node (ref "F5") (pin "2") (pinfunction "2_2") (pintype "passive"))
      (node (ref "F6") (pin "1") (pinfunction "1_1") (pintype "passive"))
      (node (ref "F6") (pin "2") (pinfunction "2_2") (pintype "passive"))
      (node (ref "F7") (pin "1") (pinfunction "1_1") (pintype "passive"))
      (node (ref "F7") (pin "2") (pinfunction "2_2") (pintype "passive"))
      (node (ref "F8") (pin "1") (pinfunction "1_1") (pintype "passive"))
      (node (ref "F8") (pin "2") (pinfunction "2_2") (pintype "passive"))
      (node (ref "R20") (pin "1") (pinfunction "1_1") (pintype "passive"))
      (node (ref "U6") (pin "1") (pinfunction "DIR_1") (pintype "passive"))
      (node (ref "U6") (pin "20") (pinfunction "VCC_20") (pintype "passive"))
    )
    (net (code "52") (name "unconnected-(SW2-B-Pad2)") (class "Default")
      (node (ref "SW2") (pin "2") (pinfunction "B_2") (pintype "passive"))
    )
    (net (code "53") (name "unconnected-(SW2-C-Pad3)") (class "Default")
      (node (ref "SW2") (pin "3") (pinfunction "C_3") (pintype "passive"))
    )
    (net (code "54") (name "unconnected-(U1-3V3_EN-Pad37)") (class "Default")
      (node (ref "U1") (pin "37") (pinfunction "3V3_EN_37") (pintype "passive"))
    )
    (net (code "55") (name "unconnected-(U1-ADC_VREF-Pad35)") (class "Default")
      (node (ref "U1") (pin "35") (pinfunction "ADC_VREF_35") (pintype "passive"))
    )
    (net (code "56") (name "unconnected-(U1-GND-Pad18)") (class "Default")
      (node (ref "U1") (pin "18") (pinfunction "GND_18") (pintype "passive"))
    )
    (net (code "57") (name "unconnected-(U1-GND-Pad23)") (class "Default")
      (node (ref "U1") (pin "23") (pinfunction "GND_23") (pintype "passive"))
    )
    (net (code "58") (name "unconnected-(U1-GP10_SPI1SCK_I2C1SDA-Pad14)") (class "Default")
      (node (ref "U1") (pin "14") (pinfunction "GP10_SPI1SCK_I2C1SDA_14") (pintype "passive"))
    )
    (net (code "59") (name "unconnected-(U1-GP11_SPI1TX_I2C1SCL-Pad15)") (class "Default")
      (node (ref "U1") (pin "15") (pinfunction "GP11_SPI1TX_I2C1SCL_15") (pintype "passive"))
    )
    (net (code "60") (name "unconnected-(U1-GP12_SPI1RX_I2C0SDA_UART0TX-Pad16)") (class "Default")
      (node (ref "U1") (pin "16") (pinfunction "GP12_SPI1RX_I2C0SDA_UART0TX_16") (pintype "passive"))
    )
    (net (code "61") (name "unconnected-(U1-GP13_SPI1CSn_I2C0SCL_UART0RX-Pad17)") (class "Default")
      (node (ref "U1") (pin "17") (pinfunction "GP13_SPI1CSn_I2C0SCL_UART0RX_17") (pintype "passive"))
    )
    (net (code "62") (name "unconnected-(U1-GP14_SPI1SCK_I2C1SDA-Pad19)") (class "Default")
      (node (ref "U1") (pin "19") (pinfunction "GP14_SPI1SCK_I2C1SDA_19") (pintype "passive"))
    )
    (net (code "63") (name "unconnected-(U1-GP15_SPI1TX_I2C1SCL-Pad20)") (class "Default")
      (node (ref "U1") (pin "20") (pinfunction "GP15_SPI1TX_I2C1SCL_20") (pintype "passive"))
    )
    (net (code "64") (name "unconnected-(U1-GP16_SPI0RX_UART0RX-Pad21)") (class "Default")
      (node (ref "U1") (pin "21") (pinfunction "GP16_SPI0RX_UART0RX_21") (pintype "passive"))
    )
    (net (code "65") (name "unconnected-(U1-GP17_SPI0CSn_UART0TX-Pad22)") (class "Default")
      (node (ref "U1") (pin "22") (pinfunction "GP17_SPI0CSn_UART0TX_22") (pintype "passive"))
    )
    (net (code "66") (name "unconnected-(U1-GP18_SPI0SCK_I2C1SDA-Pad24)") (class "Default")
      (node (ref "U1") (pin "24") (pinfunction "GP18_SPI0SCK_I2C1SDA_24") (pintype "passive"))
    )
    (net (code "67") (name "unconnected-(U1-GP19_SPI0TX_I2C1SCL-Pad25)") (class "Default")
      (node (ref "U1") (pin "25") (pinfunction "GP19_SPI0TX_I2C1SCL_25") (pintype "passive"))
    )
    (net (code "68") (name "unconnected-(U1-GP26_ADC0_I2C1SDA-Pad31)") (class "Default")
      (node (ref "U1") (pin "31") (pinfunction "GP26_ADC0_I2C1SDA_31") (pintype "passive"))
    )
    (net (code "69") (name "unconnected-(U1-GP27_ADC1_I2C1SCL-Pad32)") (class "Default")
      (node (ref "U1") (pin "32") (pinfunction "GP27_ADC1_I2C1SCL_32") (pintype "passive"))
    )
    (net (code "70") (name "unconnected-(U1-GP28_ADC2-Pad34)") (class "Default")
      (node (ref "U1") (pin "34") (pinfunction "GP28_ADC2_34") (pintype "passive"))
    )
    (net (code "71") (name "unconnected-(U1-PadTP1)") (class "Default")
      (node (ref "U1") (pin "TP1") (pinfunction "TP1_TP1") (pintype "passive"))
    )
    (net (code "72") (name "unconnected-(U1-PadTP2)") (class "Default")
      (node (ref "U1") (pin "TP2") (pinfunction "TP2_TP2") (pintype "passive"))
    )
    (net (code "73") (name "unconnected-(U1-PadTP3)") (class "Default")
      (node (ref "U1") (pin "TP3") (pinfunction "TP3_TP3") (pintype "passive"))
    )
    (net (code "74") (name "unconnected-(U1-PadTP4)") (class "Default")
      (node (ref "U1") (pin "TP4") (pinfunction "TP4_TP4") (pintype "passive"))
    )
    (net (code "75") (name "unconnected-(U1-PadTP5)") (class "Default")
      (node (ref "U1") (pin "TP5") (pinfunction "TP5_TP5") (pintype "passive"))
    )
    (net (code "76") (name "unconnected-(U1-PadTP6)") (class "Default")
      (node (ref "U1") (pin "TP6") (pinfunction "TP6_TP6") (pintype "passive"))
    )
    (net (code "77") (name "unconnected-(U1-VBUS-Pad40)") (class "Default")
      (node (ref "U1") (pin "40") (pinfunction "VBUS_40") (pintype "passive"))
    )
    (net (code "78") (name "unconnected-(U4-B5-Pad14)") (class "Default")
      (node (ref "U4") (pin "14") (pinfunction "B5_14") (pintype "passive"))
    )
    (net (code "79") (name "unconnected-(U4-B6-Pad13)") (class "Default")
      (node (ref "U4") (pin "13") (pinfunction "B6_13") (pintype "passive"))
    )
    (net (code "80") (name "unconnected-(U4-B7-Pad12)") (class "Default")
      (node (ref "U4") (pin "12") (pinfunction "B7_12") (pintype "passive"))
    )
    (net (code "81") (name "unconnected-(U4-B8-Pad11)") (class "Default")
      (node (ref "U4") (pin "11") (pinfunction "B8_11") (pintype "passive"))
    )
    (net (code "82") (name "unconnected-(U5A-32kHz-Pad1)") (class "Default")
      (node (ref "U5") (pin "1") (pinfunction "32kHz_1") (pintype "passive"))
    )
    (net (code "83") (name "unconnected-(U5A-INTSQW-Pad3)") (class "Default")
      (node (ref "U5") (pin "3") (pinfunction "INTSQW_3") (pintype "passive"))
    )
    (net (code "84") (name "unconnected-(U5A-RST-Pad4)") (class "Default")
      (node (ref "U5") (pin "4") (pinfunction "RST_4") (pintype "passive"))
    )
    (net (code "85") (name "unconnected-(U6-B5-Pad14)") (class "Default")
      (node (ref "U6") (pin "14") (pinfunction "B5_14") (pintype "passive"))
    )
    (net (code "86") (name "unconnected-(U6-B6-Pad13)") (class "Default")
      (node (ref "U6") (pin "13") (pinfunction "B6_13") (pintype "passive"))
    )
    (net (code "87") (name "unconnected-(U6-B7-Pad12)") (class "Default")
      (node (ref "U6") (pin "12") (pinfunction "B7_12") (pintype "passive"))
    )
    (net (code "88") (name "unconnected-(U6-B8-Pad11)") (class "Default")
      (node (ref "U6") (pin "11") (pinfunction "B8_11") (pintype "passive"))
    )
  )
)
